# 348.net
KiCad netlist of a schematic drawn in Altium Designer
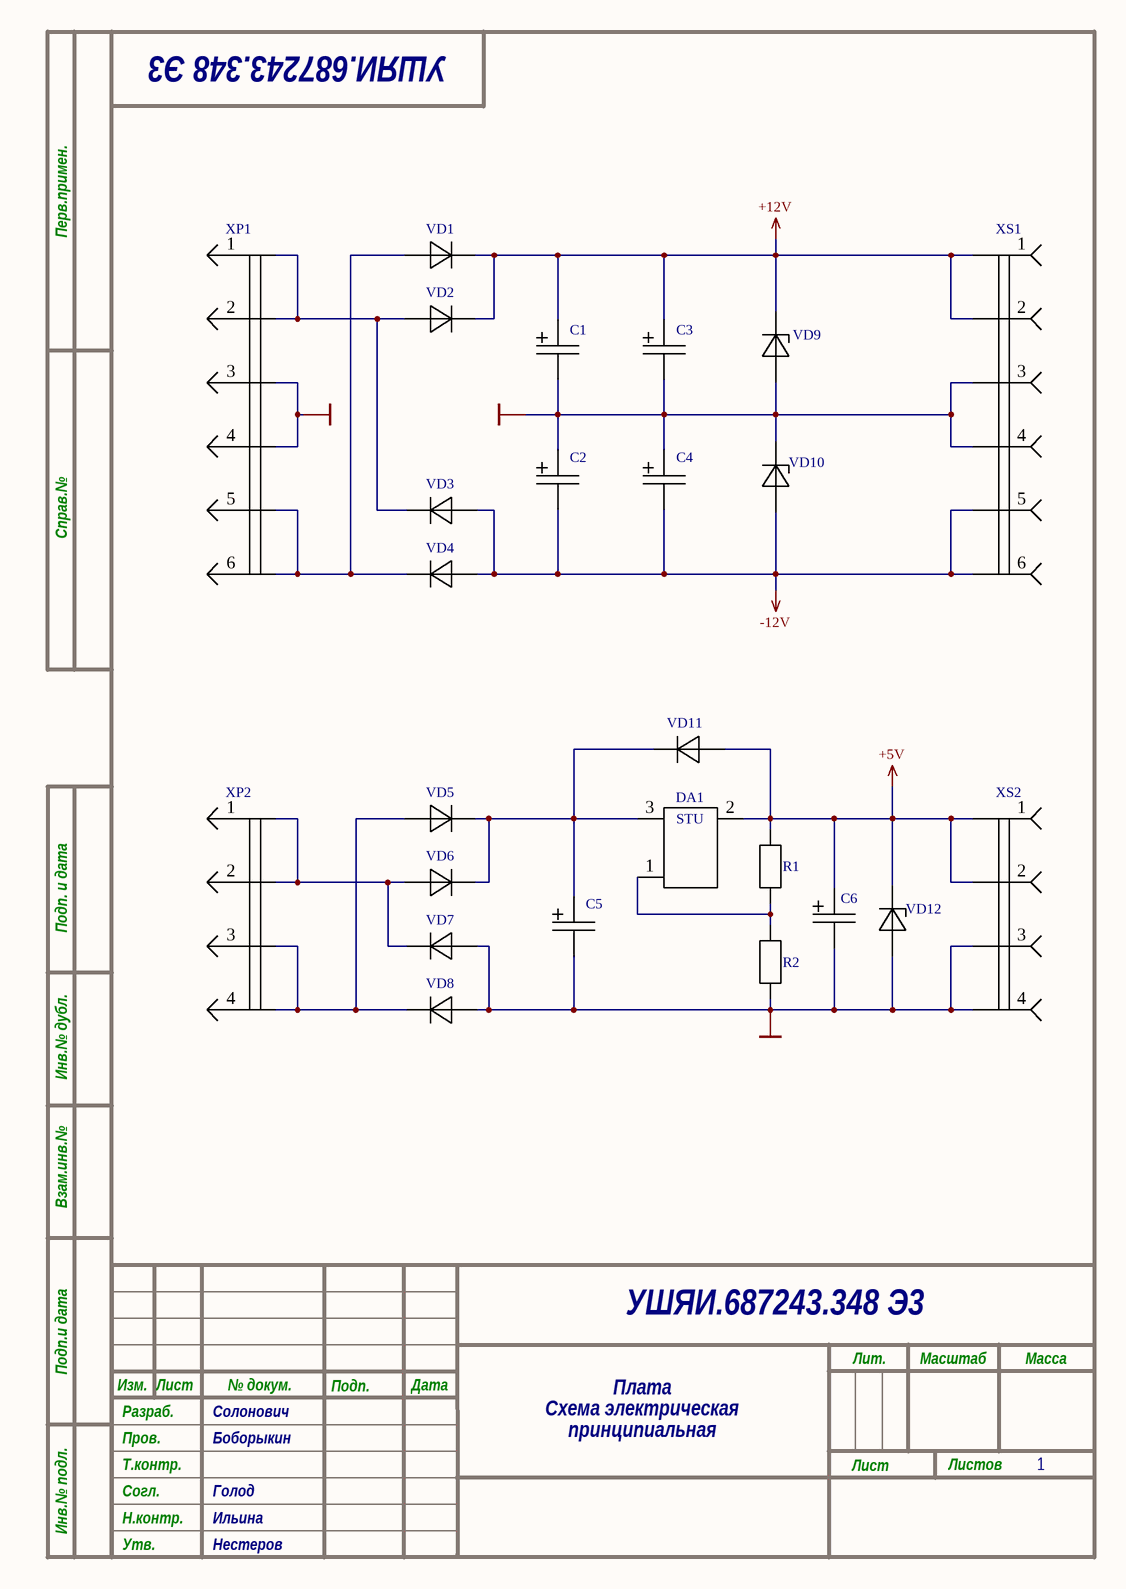
[diagram p0: Плата 348.SchDoc]

(export (version "E")
  (design (tool "Eeschema 10.0.6"))
  (components
    (comp (ref "C1") (value "Полярный конденсатор") (libsource (lib "Schlib1") (part "Полярный конденсатор")))
    (comp (ref "C2") (value "Полярный конденсатор") (libsource (lib "Schlib1") (part "Полярный конденсатор")))
    (comp (ref "C3") (value "Полярный конденсатор") (libsource (lib "Schlib1") (part "Полярный конденсатор")))
    (comp (ref "C4") (value "Полярный конденсатор") (libsource (lib "Schlib1") (part "Полярный конденсатор")))
    (comp (ref "C5") (value "Полярный конденсатор") (libsource (lib "Schlib1") (part "Полярный конденсатор")))
    (comp (ref "C6") (value "Полярный конденсатор") (libsource (lib "Schlib1") (part "Полярный конденсатор")))
    (comp (ref "DA1") (value "Микросхема") (libsource (lib "Schlib1") (part "Микросхема")))
    (comp (ref "R1") (value "Резистор мини") (libsource (lib "Schlib1") (part "Резистор мини")))
    (comp (ref "R2") (value "Резистор мини") (libsource (lib "Schlib1") (part "Резистор мини")))
    (comp (ref "VD1") (value "Диод") (libsource (lib "Schlib1") (part "Диод")))
    (comp (ref "VD2") (value "Диод") (libsource (lib "Schlib1") (part "Диод")))
    (comp (ref "VD3") (value "Диод") (libsource (lib "Schlib1") (part "Диод")))
    (comp (ref "VD4") (value "Диод") (libsource (lib "Schlib1") (part "Диод")))
    (comp (ref "VD5") (value "Диод") (libsource (lib "Schlib1") (part "Диод")))
    (comp (ref "VD6") (value "Диод") (libsource (lib "Schlib1") (part "Диод")))
    (comp (ref "VD7") (value "Диод") (libsource (lib "Schlib1") (part "Диод")))
    (comp (ref "VD8") (value "Диод") (libsource (lib "Schlib1") (part "Диод")))
    (comp (ref "VD9") (value "Стабилитрон") (libsource (lib "Schlib1") (part "Стабилитрон")))
    (comp (ref "VD10") (value "Стабилитрон") (libsource (lib "Schlib1") (part "Стабилитрон")))
    (comp (ref "VD11") (value "Диод") (libsource (lib "Schlib1") (part "Диод")))
    (comp (ref "VD12") (value "Стабилитрон") (libsource (lib "Schlib1") (part "Стабилитрон")))
    (comp (ref "XP1") (value "Вилка 6 пин") (libsource (lib "Schlib1") (part "Вилка 6 пин")))
    (comp (ref "XP2") (value "Вилка 4 пин") (libsource (lib "Schlib1") (part "Вилка 4 пин")))
    (comp (ref "XS1") (value "Розетка 6 пин") (libsource (lib "Schlib1") (part "Розетка 6 пин")))
    (comp (ref "XS2") (value "Розетка 4 пин") (libsource (lib "Schlib1") (part "Розетка 4 пин")))
  )
  (nets
    (net (code "1") (name "+5V") (class "Default")
      (node (ref "C6") (pin "1") (pintype "power_in"))
      (node (ref "DA1") (pin "2") (pintype "power_in"))
      (node (ref "R1") (pin "2") (pintype "power_in"))
      (node (ref "VD11") (pin "2") (pintype "power_in"))
      (node (ref "VD12") (pin "1") (pintype "power_in"))
      (node (ref "XS2") (pin "1") (pintype "power_in"))
      (node (ref "XS2") (pin "2") (pintype "power_in"))
    )
    (net (code "2") (name "+12V") (class "Default")
      (node (ref "C1") (pin "1") (pintype "power_in"))
      (node (ref "C3") (pin "1") (pintype "power_in"))
      (node (ref "VD1") (pin "1") (pintype "power_in"))
      (node (ref "VD2") (pin "1") (pintype "power_in"))
      (node (ref "VD9") (pin "1") (pintype "power_in"))
      (node (ref "XS1") (pin "1") (pintype "power_in"))
      (node (ref "XS1") (pin "2") (pintype "power_in"))
    )
    (net (code "3") (name "-12V") (class "Default")
      (node (ref "C2") (pin "2") (pintype "power_in"))
      (node (ref "C4") (pin "2") (pintype "power_in"))
      (node (ref "VD10") (pin "2") (pintype "power_in"))
      (node (ref "VD3") (pin "2") (pintype "power_in"))
      (node (ref "VD4") (pin "2") (pintype "power_in"))
      (node (ref "XS1") (pin "5") (pintype "power_in"))
      (node (ref "XS1") (pin "6") (pintype "power_in"))
    )
    (net (code "4") (name "GND") (class "Default")
      (node (ref "C1") (pin "2") (pintype "power_in"))
      (node (ref "C2") (pin "1") (pintype "power_in"))
      (node (ref "C3") (pin "2") (pintype "power_in"))
      (node (ref "C4") (pin "1") (pintype "power_in"))
      (node (ref "C5") (pin "2") (pintype "power_in"))
      (node (ref "C6") (pin "2") (pintype "power_in"))
      (node (ref "R2") (pin "1") (pintype "power_in"))
      (node (ref "VD10") (pin "1") (pintype "power_in"))
      (node (ref "VD12") (pin "2") (pintype "power_in"))
      (node (ref "VD7") (pin "2") (pintype "power_in"))
      (node (ref "VD8") (pin "2") (pintype "power_in"))
      (node (ref "VD9") (pin "2") (pintype "power_in"))
      (node (ref "XP1") (pin "3") (pintype "power_in"))
      (node (ref "XP1") (pin "4") (pintype "power_in"))
      (node (ref "XS1") (pin "3") (pintype "power_in"))
      (node (ref "XS1") (pin "4") (pintype "power_in"))
      (node (ref "XS2") (pin "3") (pintype "power_in"))
      (node (ref "XS2") (pin "4") (pintype "power_in"))
    )
    (net (code "5") (name "Net-(C5-Pad1)") (class "Default")
      (node (ref "C5") (pin "1") (pintype "power_in"))
      (node (ref "DA1") (pin "3") (pintype "power_in"))
      (node (ref "VD11") (pin "1") (pintype "power_in"))
      (node (ref "VD5") (pin "1") (pintype "power_in"))
      (node (ref "VD6") (pin "1") (pintype "power_in"))
    )
    (net (code "6") (name "Net-(DA1-Pad1)") (class "Default")
      (node (ref "DA1") (pin "1") (pintype "power_in"))
      (node (ref "R1") (pin "1") (pintype "power_in"))
      (node (ref "R2") (pin "2") (pintype "power_in"))
    )
    (net (code "7") (name "Net-(VD1-Pad2)") (class "Default")
      (node (ref "VD1") (pin "2") (pintype "power_in"))
      (node (ref "VD4") (pin "1") (pintype "power_in"))
      (node (ref "XP1") (pin "5") (pintype "power_in"))
      (node (ref "XP1") (pin "6") (pintype "power_in"))
    )
    (net (code "8") (name "Net-(VD2-Pad2)") (class "Default")
      (node (ref "VD2") (pin "2") (pintype "power_in"))
      (node (ref "VD3") (pin "1") (pintype "power_in"))
      (node (ref "XP1") (pin "1") (pintype "power_in"))
      (node (ref "XP1") (pin "2") (pintype "power_in"))
    )
    (net (code "9") (name "Net-(VD5-Pad2)") (class "Default")
      (node (ref "VD5") (pin "2") (pintype "power_in"))
      (node (ref "VD8") (pin "1") (pintype "power_in"))
      (node (ref "XP2") (pin "3") (pintype "power_in"))
      (node (ref "XP2") (pin "4") (pintype "power_in"))
    )
    (net (code "10") (name "Net-(VD6-Pad2)") (class "Default")
      (node (ref "VD6") (pin "2") (pintype "power_in"))
      (node (ref "VD7") (pin "1") (pintype "power_in"))
      (node (ref "XP2") (pin "1") (pintype "power_in"))
      (node (ref "XP2") (pin "2") (pintype "power_in"))
    )
  )
)
